# bleumaus-nrf51822-mk-1_0_2.net
KiCad netlist of a schematic drawn in EAGLE
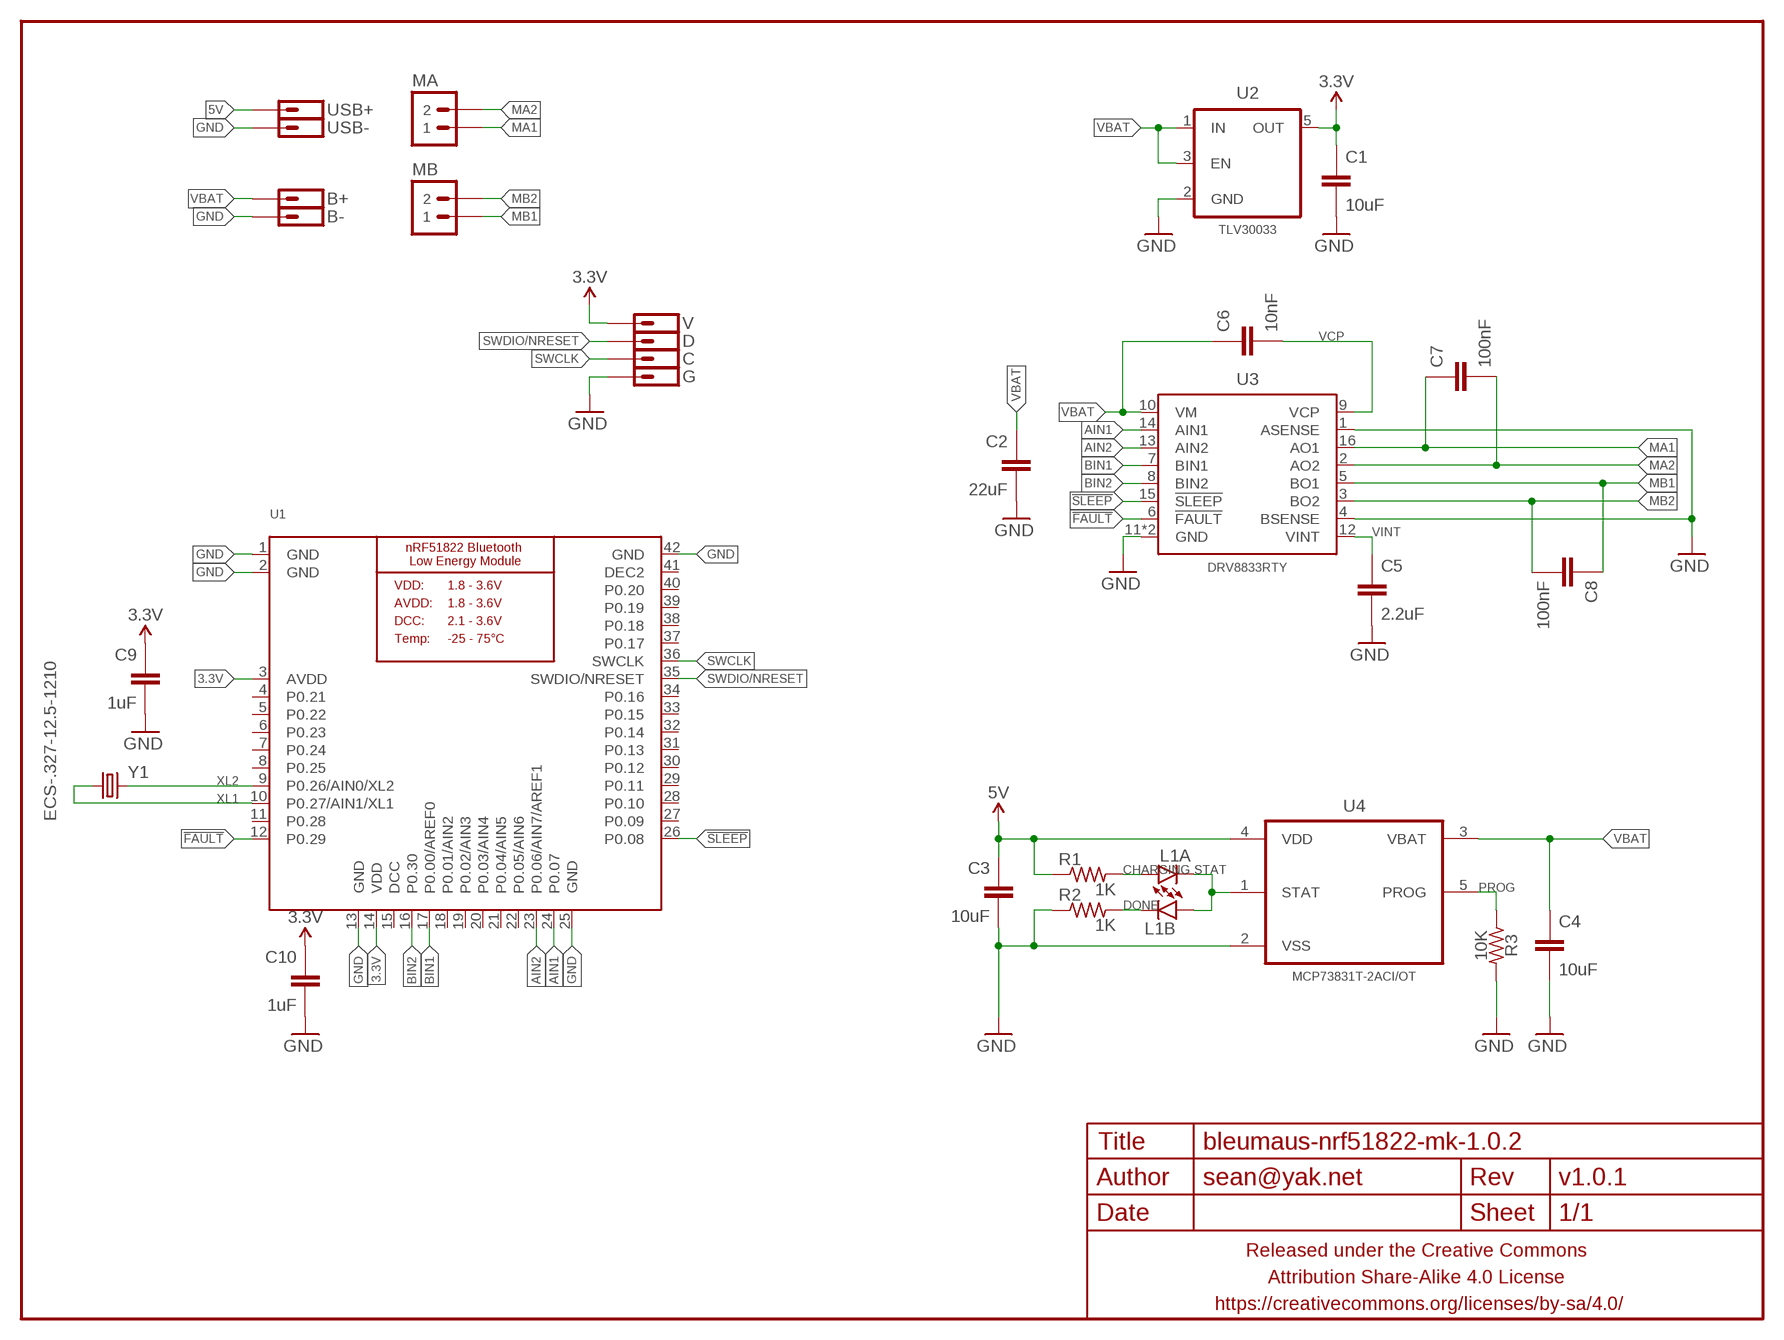
[diagram p0: schematic, sheet 1]

(export (version "E")
  (design (tool "Eeschema 10.0.6"))
  (components
    (comp (ref "B+")
      (value "M01SMD-1DIA")
      (footprint "eagle-import:1X01-SMD-1MM-DIA")
      (libsource (lib "eagle-import") (part "M01SMD-1DIA"))
    )
    (comp (ref "B-")
      (value "M01SMD-1DIA")
      (footprint "eagle-import:1X01-SMD-1MM-DIA")
      (libsource (lib "eagle-import") (part "M01SMD-1DIA"))
    )
    (comp (ref "C")
      (value "M01SMD-1DIA")
      (footprint "eagle-import:1X01-SMD-1MM-DIA")
      (libsource (lib "eagle-import") (part "M01SMD-1DIA"))
    )
    (comp (ref "C1")
      (value "10uF")
      (footprint "eagle-import:C0402")
      (libsource (lib "eagle-import") (part "CAPACITOR-CERAMICC0402"))
    )
    (comp (ref "C2")
      (value "22uF")
      (footprint "eagle-import:C1206")
      (libsource (lib "eagle-import") (part "CAPACITOR-CERAMICC1206"))
    )
    (comp (ref "C3")
      (value "10uF")
      (footprint "eagle-import:C0402")
      (libsource (lib "eagle-import") (part "CAPACITOR-CERAMICC0402"))
    )
    (comp (ref "C4")
      (value "10uF")
      (footprint "eagle-import:C0402")
      (libsource (lib "eagle-import") (part "CAPACITOR-CERAMICC0402"))
    )
    (comp (ref "C5")
      (value "2.2uF")
      (footprint "eagle-import:C0402")
      (libsource (lib "eagle-import") (part "CAPACITOR-CERAMICC0402"))
    )
    (comp (ref "C6")
      (value "10nF")
      (footprint "eagle-import:C0402")
      (libsource (lib "eagle-import") (part "CAPACITOR-CERAMICC0402"))
    )
    (comp (ref "C7")
      (value "100nF")
      (footprint "eagle-import:C0402")
      (libsource (lib "eagle-import") (part "CAPACITOR-CERAMICC0402"))
    )
    (comp (ref "C8")
      (value "100nF")
      (footprint "eagle-import:C0402")
      (libsource (lib "eagle-import") (part "CAPACITOR-CERAMICC0402"))
    )
    (comp (ref "C9")
      (value "1uF")
      (footprint "eagle-import:C0402")
      (libsource (lib "eagle-import") (part "CAPACITOR-CERAMICC0402"))
    )
    (comp (ref "C10")
      (value "1uF")
      (footprint "eagle-import:C0402")
      (libsource (lib "eagle-import") (part "CAPACITOR-CERAMICC0402"))
    )
    (comp (ref "D")
      (value "M01SMD-1DIA")
      (footprint "eagle-import:1X01-SMD-1MM-DIA")
      (libsource (lib "eagle-import") (part "M01SMD-1DIA"))
    )
    (comp (ref "FRAME1")
      (value "FRAME-LETTERNO_PACKAGE")
      (footprint "eagle-import:DUMMY")
      (fields
        (field (name "DESIGNER") "sean@yak.net")
        (field (name "VERSION") "v1.0.1")
        (field (name "DESIGNER_1") "sean@yak.net")
        (field (name "VERSION_1") "v1.0.1")
      )
      (libsource (lib "eagle-import") (part "FRAME-LETTERNO_PACKAGE"))
    )
    (comp (ref "G")
      (value "M01SMD-1DIA")
      (footprint "eagle-import:1X01-SMD-1MM-DIA")
      (libsource (lib "eagle-import") (part "M01SMD-1DIA"))
    )
    (comp (ref "L1")
      (value "LED-BICOLORLNJ167W87RA")
      (footprint "eagle-import:LNJ167W87RA")
      (libsource (lib "eagle-import") (part "LED-BICOLORLNJ167W87RA"))
    )
    (comp (ref "MA")
      (value "M02PTH-2MM")
      (footprint "eagle-import:1X02-2MM-PTH")
      (libsource (lib "eagle-import") (part "M02PTH-2MM"))
    )
    (comp (ref "MB")
      (value "M02PTH-2MM")
      (footprint "eagle-import:1X02-2MM-PTH")
      (libsource (lib "eagle-import") (part "M02PTH-2MM"))
    )
    (comp (ref "R1")
      (value "1K")
      (footprint "eagle-import:R0402")
      (libsource (lib "eagle-import") (part "RESISTORR0402"))
    )
    (comp (ref "R2")
      (value "1K")
      (footprint "eagle-import:R0402")
      (libsource (lib "eagle-import") (part "RESISTORR0402"))
    )
    (comp (ref "R3")
      (value "10K")
      (footprint "eagle-import:R0402")
      (libsource (lib "eagle-import") (part "RESISTORR0402"))
    )
    (comp (ref "U1")
      (value "NRF51822_MODULE_MDBT40")
      (footprint "eagle-import:BLE_MODULE_RAYTAC_MDBT40")
      (libsource (lib "eagle-import") (part "NRF51822_MODULE_MDBT40"))
    )
    (comp (ref "U2")
      (value "TLV30033")
      (footprint "eagle-import:SC70-TIGHTER")
      (libsource (lib "eagle-import") (part "V_REG_ENTLV700XXDCK-TIGHTER"))
    )
    (comp (ref "U3")
      (value "DRV8833RTY")
      (footprint "eagle-import:PWQFN-16")
      (libsource (lib "eagle-import") (part "DRV8833RTY"))
    )
    (comp (ref "U4")
      (value "MCP73831T-2ACI/OT")
      (footprint "eagle-import:SOT95P280X145-5N")
      (libsource (lib "eagle-import") (part "MCP73831T-2ACI/OT"))
    )
    (comp (ref "USB+")
      (value "M01SMD-1DIA")
      (footprint "eagle-import:1X01-SMD-1MM-DIA")
      (libsource (lib "eagle-import") (part "M01SMD-1DIA"))
    )
    (comp (ref "USB-")
      (value "M01SMD-1DIA")
      (footprint "eagle-import:1X01-SMD-1MM-DIA")
      (libsource (lib "eagle-import") (part "M01SMD-1DIA"))
    )
    (comp (ref "V")
      (value "M01SMD-1DIA")
      (footprint "eagle-import:1X01-SMD-1MM-DIA")
      (libsource (lib "eagle-import") (part "M01SMD-1DIA"))
    )
    (comp (ref "Y1")
      (value "ECS-.327-12.5-1210")
      (footprint "eagle-import:CRYSTAL-1X1.2MM")
      (libsource (lib "eagle-import") (part "CRYSTAL1X1.2MM"))
    )
  )
  (nets
    (net (code "1") (name "/CHARGING") (class "Default")
      (node (ref "L1") (pin "P$1") (pinfunction "A_P$1") (pintype "passive"))
      (node (ref "R1") (pin "2") (pinfunction "2_2") (pintype "passive"))
    )
    (net (code "2") (name "/DCC") (class "Default")
      (node (ref "U1") (pin "15") (pinfunction "DCC_15") (pintype "power_in"))
    )
    (net (code "3") (name "/DEC2") (class "Default")
      (node (ref "U1") (pin "41") (pinfunction "DEC2_41") (pintype "power_in"))
    )
    (net (code "4") (name "/DONE") (class "Default")
      (node (ref "L1") (pin "P$3") (pinfunction "C_P$3") (pintype "passive"))
      (node (ref "R2") (pin "2") (pinfunction "2_2") (pintype "passive"))
    )
    (net (code "5") (name "/PROG") (class "Default")
      (node (ref "R3") (pin "1") (pinfunction "1_1") (pintype "passive"))
      (node (ref "U4") (pin "5") (pinfunction "PROG_5") (pintype "input"))
    )
    (net (code "6") (name "/STAT") (class "Default")
      (node (ref "L1") (pin "P$2") (pinfunction "A_P$2") (pintype "passive"))
      (node (ref "L1") (pin "P$4") (pinfunction "C_P$4") (pintype "passive"))
      (node (ref "U4") (pin "1") (pinfunction "STAT_1") (pintype "output"))
    )
    (net (code "7") (name "/VCP") (class "Default")
      (node (ref "C6") (pin "2") (pinfunction "2_2") (pintype "passive"))
      (node (ref "U3") (pin "9") (pinfunction "VCP_9") (pintype "bidirectional"))
    )
    (net (code "8") (name "/VINT") (class "Default")
      (node (ref "C5") (pin "1") (pinfunction "1_1") (pintype "passive"))
      (node (ref "U3") (pin "12") (pinfunction "VINT_12") (pintype "bidirectional"))
    )
    (net (code "9") (name "/XL1") (class "Default")
      (node (ref "U1") (pin "10") (pinfunction "P0.27/AIN1/XL1_10") (pintype "bidirectional"))
      (node (ref "Y1") (pin "1") (pinfunction "1_1") (pintype "passive"))
    )
    (net (code "10") (name "/XL2") (class "Default")
      (node (ref "U1") (pin "9") (pinfunction "P0.26/AIN0/XL2_9") (pintype "bidirectional"))
      (node (ref "Y1") (pin "2") (pinfunction "2_2") (pintype "passive"))
    )
    (net (code "11") (name "/~{FAULT}") (class "Default")
      (node (ref "U1") (pin "12") (pinfunction "P0.29_12") (pintype "bidirectional"))
      (node (ref "U3") (pin "6") (pinfunction "~{FAULT}_6") (pintype "output"))
    )
    (net (code "12") (name "/~{SLEEP}") (class "Default")
      (node (ref "U1") (pin "26") (pinfunction "P0.08_26") (pintype "bidirectional"))
      (node (ref "U3") (pin "15") (pinfunction "~{SLEEP}_15") (pintype "input"))
    )
    (net (code "13") (name "3.3V") (class "Default")
      (node (ref "C1") (pin "1") (pinfunction "1_1") (pintype "passive"))
      (node (ref "C10") (pin "1") (pinfunction "1_1") (pintype "passive"))
      (node (ref "C9") (pin "1") (pinfunction "1_1") (pintype "passive"))
      (node (ref "U1") (pin "14") (pinfunction "VDD_14") (pintype "power_in"))
      (node (ref "U1") (pin "3") (pinfunction "AVDD_3") (pintype "power_in"))
      (node (ref "U2") (pin "5") (pinfunction "OUT_5") (pintype "passive"))
      (node (ref "V") (pin "P$1") (pinfunction "1_P$1") (pintype "passive"))
    )
    (net (code "14") (name "5V") (class "Default")
      (node (ref "C3") (pin "1") (pinfunction "1_1") (pintype "passive"))
      (node (ref "R1") (pin "1") (pinfunction "1_1") (pintype "passive"))
      (node (ref "U4") (pin "4") (pinfunction "VDD_4") (pintype "power_in"))
      (node (ref "USB+") (pin "P$1") (pinfunction "1_P$1") (pintype "passive"))
    )
    (net (code "15") (name "AIN1") (class "Default")
      (node (ref "U1") (pin "24") (pinfunction "P0.07_24") (pintype "bidirectional"))
      (node (ref "U3") (pin "14") (pinfunction "AIN1_14") (pintype "input"))
    )
    (net (code "16") (name "AIN2") (class "Default")
      (node (ref "U1") (pin "23") (pinfunction "P0.06/AIN7/AREF1_23") (pintype "bidirectional"))
      (node (ref "U3") (pin "13") (pinfunction "AIN2_13") (pintype "input"))
    )
    (net (code "17") (name "BIN1") (class "Default")
      (node (ref "U1") (pin "17") (pinfunction "P0.00/AREF0_17") (pintype "bidirectional"))
      (node (ref "U3") (pin "7") (pinfunction "BIN1_7") (pintype "input"))
    )
    (net (code "18") (name "BIN2") (class "Default")
      (node (ref "U1") (pin "16") (pinfunction "P0.30_16") (pintype "bidirectional"))
      (node (ref "U3") (pin "8") (pinfunction "BIN2_8") (pintype "input"))
    )
    (net (code "19") (name "GND") (class "Default")
      (node (ref "B-") (pin "P$1") (pinfunction "1_P$1") (pintype "passive"))
      (node (ref "C1") (pin "2") (pinfunction "2_2") (pintype "passive"))
      (node (ref "C10") (pin "2") (pinfunction "2_2") (pintype "passive"))
      (node (ref "C2") (pin "2") (pinfunction "2_2") (pintype "passive"))
      (node (ref "C3") (pin "2") (pinfunction "2_2") (pintype "passive"))
      (node (ref "C4") (pin "2") (pinfunction "2_2") (pintype "passive"))
      (node (ref "C5") (pin "2") (pinfunction "2_2") (pintype "passive"))
      (node (ref "C9") (pin "2") (pinfunction "2_2") (pintype "passive"))
      (node (ref "G") (pin "P$1") (pinfunction "1_P$1") (pintype "passive"))
      (node (ref "R2") (pin "1") (pinfunction "1_1") (pintype "passive"))
      (node (ref "R3") (pin "2") (pinfunction "2_2") (pintype "passive"))
      (node (ref "U1") (pin "1") (pinfunction "GND_1") (pintype "power_in"))
      (node (ref "U1") (pin "13") (pinfunction "GND_13") (pintype "power_in"))
      (node (ref "U1") (pin "2") (pinfunction "GND_2") (pintype "power_in"))
      (node (ref "U1") (pin "25") (pinfunction "GND_25") (pintype "power_in"))
      (node (ref "U1") (pin "42") (pinfunction "GND_42") (pintype "power_in"))
      (node (ref "U2") (pin "2") (pinfunction "GND_2") (pintype "input"))
      (node (ref "U3") (pin "1") (pinfunction "ASENSE_1") (pintype "bidirectional"))
      (node (ref "U3") (pin "11") (pinfunction "GND_11") (pintype "bidirectional"))
      (node (ref "U3") (pin "17") (pinfunction "GND_17") (pintype "bidirectional"))
      (node (ref "U3") (pin "4") (pinfunction "BSENSE_4") (pintype "bidirectional"))
      (node (ref "U4") (pin "2") (pinfunction "VSS_2") (pintype "power_in"))
      (node (ref "USB-") (pin "P$1") (pinfunction "1_P$1") (pintype "passive"))
    )
    (net (code "20") (name "MA1") (class "Default")
      (node (ref "C7") (pin "1") (pinfunction "1_1") (pintype "passive"))
      (node (ref "MA") (pin "P$1") (pinfunction "1_P$1") (pintype "passive"))
      (node (ref "U3") (pin "16") (pinfunction "AO1_16") (pintype "bidirectional"))
    )
    (net (code "21") (name "MA2") (class "Default")
      (node (ref "C7") (pin "2") (pinfunction "2_2") (pintype "passive"))
      (node (ref "MA") (pin "P$2") (pinfunction "2_P$2") (pintype "passive"))
      (node (ref "U3") (pin "2") (pinfunction "AO2_2") (pintype "bidirectional"))
    )
    (net (code "22") (name "MB1") (class "Default")
      (node (ref "C8") (pin "1") (pinfunction "1_1") (pintype "passive"))
      (node (ref "MB") (pin "P$1") (pinfunction "1_P$1") (pintype "passive"))
      (node (ref "U3") (pin "5") (pinfunction "BO1_5") (pintype "bidirectional"))
    )
    (net (code "23") (name "MB2") (class "Default")
      (node (ref "C8") (pin "2") (pinfunction "2_2") (pintype "passive"))
      (node (ref "MB") (pin "P$2") (pinfunction "2_P$2") (pintype "passive"))
      (node (ref "U3") (pin "3") (pinfunction "BO2_3") (pintype "bidirectional"))
    )
    (net (code "24") (name "SWCLK") (class "Default")
      (node (ref "C") (pin "P$1") (pinfunction "1_P$1") (pintype "passive"))
      (node (ref "U1") (pin "36") (pinfunction "SWCLK_36") (pintype "bidirectional"))
    )
    (net (code "25") (name "SWDIO{slash}NRESET") (class "Default")
      (node (ref "D") (pin "P$1") (pinfunction "1_P$1") (pintype "passive"))
      (node (ref "U1") (pin "35") (pinfunction "SWDIO/NRESET_35") (pintype "bidirectional"))
    )
    (net (code "26") (name "VBAT") (class "Default")
      (node (ref "B+") (pin "P$1") (pinfunction "1_P$1") (pintype "passive"))
      (node (ref "C2") (pin "1") (pinfunction "1_1") (pintype "passive"))
      (node (ref "C4") (pin "1") (pinfunction "1_1") (pintype "passive"))
      (node (ref "C6") (pin "1") (pinfunction "1_1") (pintype "passive"))
      (node (ref "U2") (pin "1") (pinfunction "IN_1") (pintype "input"))
      (node (ref "U2") (pin "3") (pinfunction "EN_3") (pintype "input"))
      (node (ref "U3") (pin "10") (pinfunction "VM_10") (pintype "bidirectional"))
      (node (ref "U4") (pin "3") (pinfunction "VBAT_3") (pintype "output"))
    )
    (net (code "27") (name "unconnected-(U1-P0.01{slash}AIN2-Pad18)") (class "Default")
      (node (ref "U1") (pin "18") (pinfunction "P0.01/AIN2_18") (pintype "bidirectional"))
    )
    (net (code "28") (name "unconnected-(U1-P0.02{slash}AIN3-Pad19)") (class "Default")
      (node (ref "U1") (pin "19") (pinfunction "P0.02/AIN3_19") (pintype "bidirectional"))
    )
    (net (code "29") (name "unconnected-(U1-P0.03{slash}AIN4-Pad20)") (class "Default")
      (node (ref "U1") (pin "20") (pinfunction "P0.03/AIN4_20") (pintype "bidirectional"))
    )
    (net (code "30") (name "unconnected-(U1-P0.04{slash}AIN5-Pad21)") (class "Default")
      (node (ref "U1") (pin "21") (pinfunction "P0.04/AIN5_21") (pintype "bidirectional"))
    )
    (net (code "31") (name "unconnected-(U1-P0.05{slash}AIN6-Pad22)") (class "Default")
      (node (ref "U1") (pin "22") (pinfunction "P0.05/AIN6_22") (pintype "bidirectional"))
    )
    (net (code "32") (name "unconnected-(U1-P0.09-Pad27)") (class "Default")
      (node (ref "U1") (pin "27") (pinfunction "P0.09_27") (pintype "bidirectional"))
    )
    (net (code "33") (name "unconnected-(U1-P0.10-Pad28)") (class "Default")
      (node (ref "U1") (pin "28") (pinfunction "P0.10_28") (pintype "bidirectional"))
    )
    (net (code "34") (name "unconnected-(U1-P0.11-Pad29)") (class "Default")
      (node (ref "U1") (pin "29") (pinfunction "P0.11_29") (pintype "bidirectional"))
    )
    (net (code "35") (name "unconnected-(U1-P0.12-Pad30)") (class "Default")
      (node (ref "U1") (pin "30") (pinfunction "P0.12_30") (pintype "bidirectional"))
    )
    (net (code "36") (name "unconnected-(U1-P0.13-Pad31)") (class "Default")
      (node (ref "U1") (pin "31") (pinfunction "P0.13_31") (pintype "bidirectional"))
    )
    (net (code "37") (name "unconnected-(U1-P0.14-Pad32)") (class "Default")
      (node (ref "U1") (pin "32") (pinfunction "P0.14_32") (pintype "bidirectional"))
    )
    (net (code "38") (name "unconnected-(U1-P0.15-Pad33)") (class "Default")
      (node (ref "U1") (pin "33") (pinfunction "P0.15_33") (pintype "bidirectional"))
    )
    (net (code "39") (name "unconnected-(U1-P0.16-Pad34)") (class "Default")
      (node (ref "U1") (pin "34") (pinfunction "P0.16_34") (pintype "bidirectional"))
    )
    (net (code "40") (name "unconnected-(U1-P0.17-Pad37)") (class "Default")
      (node (ref "U1") (pin "37") (pinfunction "P0.17_37") (pintype "bidirectional"))
    )
    (net (code "41") (name "unconnected-(U1-P0.18-Pad38)") (class "Default")
      (node (ref "U1") (pin "38") (pinfunction "P0.18_38") (pintype "bidirectional"))
    )
    (net (code "42") (name "unconnected-(U1-P0.19-Pad39)") (class "Default")
      (node (ref "U1") (pin "39") (pinfunction "P0.19_39") (pintype "bidirectional"))
    )
    (net (code "43") (name "unconnected-(U1-P0.20-Pad40)") (class "Default")
      (node (ref "U1") (pin "40") (pinfunction "P0.20_40") (pintype "bidirectional"))
    )
    (net (code "44") (name "unconnected-(U1-P0.21-Pad4)") (class "Default")
      (node (ref "U1") (pin "4") (pinfunction "P0.21_4") (pintype "bidirectional"))
    )
    (net (code "45") (name "unconnected-(U1-P0.22-Pad5)") (class "Default")
      (node (ref "U1") (pin "5") (pinfunction "P0.22_5") (pintype "bidirectional"))
    )
    (net (code "46") (name "unconnected-(U1-P0.23-Pad6)") (class "Default")
      (node (ref "U1") (pin "6") (pinfunction "P0.23_6") (pintype "bidirectional"))
    )
    (net (code "47") (name "unconnected-(U1-P0.24-Pad7)") (class "Default")
      (node (ref "U1") (pin "7") (pinfunction "P0.24_7") (pintype "bidirectional"))
    )
    (net (code "48") (name "unconnected-(U1-P0.25-Pad8)") (class "Default")
      (node (ref "U1") (pin "8") (pinfunction "P0.25_8") (pintype "bidirectional"))
    )
    (net (code "49") (name "unconnected-(U1-P0.28-Pad11)") (class "Default")
      (node (ref "U1") (pin "11") (pinfunction "P0.28_11") (pintype "bidirectional"))
    )
  )
)
